# libs.net
KiCad netlist of a schematic drawn in Altium Designer
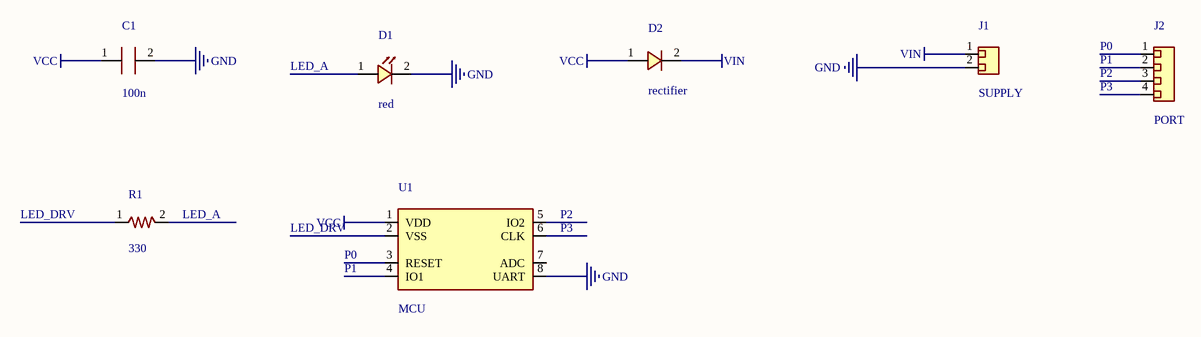
[diagram p0: libs.SchDoc]

(export (version "E")
  (design (tool "Eeschema 10.0.6"))
  (components
    (comp (ref "C1") (value "100n") (footprint "libs:Chip_0805") (libsource (lib "libs") (part "Capacitor")))
    (comp (ref "D1")
      (value "red")
      (footprint "libs:LED0603_Kingbright_APT1608SURCK")
      (libsource (lib "libs") (part "LED"))
    )
    (comp (ref "D2") (value "rectifier") (footprint "libs:DO214AC") (libsource (lib "libs") (part "Diode")))
    (comp (ref "J1")
      (value "SUPPLY")
      (footprint "libs:Header_1x2_P2.54")
      (libsource (lib "libs") (part "Connector_2"))
    )
    (comp (ref "J2")
      (value "PORT")
      (footprint "libs:Header_1x4_P2.54")
      (libsource (lib "libs") (part "Connector_4"))
    )
    (comp (ref "R1") (value "330") (footprint "libs:Chip_0603") (libsource (lib "libs") (part "Resistor")))
    (comp (ref "U1")
      (value "MCU")
      (footprint "libs:DIP8_Microchip_P")
      (libsource (lib "libs") (part "Microcontroller"))
    )
  )
  (nets
    (net (code "1") (name "/LED_A") (class "Default")
      (node (ref "D1") (pin "1") (pinfunction "A_1") (pintype "passive"))
      (node (ref "R1") (pin "2") (pinfunction "B_2") (pintype "passive"))
    )
    (net (code "2") (name "/LED_DRV") (class "Default")
      (node (ref "R1") (pin "1") (pinfunction "A_1") (pintype "passive"))
      (node (ref "U1") (pin "2") (pinfunction "VSS_2") (pintype "passive"))
    )
    (net (code "3") (name "/P0") (class "Default")
      (node (ref "J2") (pin "1") (pinfunction "Passive_1") (pintype "passive"))
      (node (ref "U1") (pin "3") (pinfunction "RESET_3") (pintype "passive"))
    )
    (net (code "4") (name "/P1") (class "Default")
      (node (ref "J2") (pin "2") (pinfunction "Passive_2") (pintype "passive"))
      (node (ref "U1") (pin "4") (pinfunction "IO1_4") (pintype "passive"))
    )
    (net (code "5") (name "/P2") (class "Default")
      (node (ref "J2") (pin "3") (pinfunction "Passive_3") (pintype "passive"))
      (node (ref "U1") (pin "5") (pinfunction "IO2_5") (pintype "passive"))
    )
    (net (code "6") (name "/P3") (class "Default")
      (node (ref "J2") (pin "4") (pinfunction "Passive_4") (pintype "passive"))
      (node (ref "U1") (pin "6") (pinfunction "CLK_6") (pintype "passive"))
    )
    (net (code "7") (name "GND") (class "Default")
      (node (ref "C1") (pin "2") (pinfunction "B_2") (pintype "passive"))
      (node (ref "D1") (pin "2") (pinfunction "K_2") (pintype "passive"))
      (node (ref "J1") (pin "2") (pinfunction "Passive_2") (pintype "passive"))
      (node (ref "U1") (pin "8") (pinfunction "UART_8") (pintype "passive"))
    )
    (net (code "8") (name "VCC") (class "Default")
      (node (ref "C1") (pin "1") (pinfunction "A_1") (pintype "passive"))
      (node (ref "D2") (pin "1") (pinfunction "A_1") (pintype "passive"))
      (node (ref "U1") (pin "1") (pinfunction "VDD_1") (pintype "passive"))
    )
    (net (code "9") (name "VIN") (class "Default")
      (node (ref "D2") (pin "2") (pinfunction "K_2") (pintype "passive"))
      (node (ref "J1") (pin "1") (pinfunction "Passive_1") (pintype "passive"))
    )
    (net (code "10") (name "unconnected-(U1-ADC-Pad7)") (class "Default")
      (node (ref "U1") (pin "7") (pinfunction "ADC_7") (pintype "passive"))
    )
  )
)
